# board.net
KiCad netlist of a schematic drawn in EAGLE
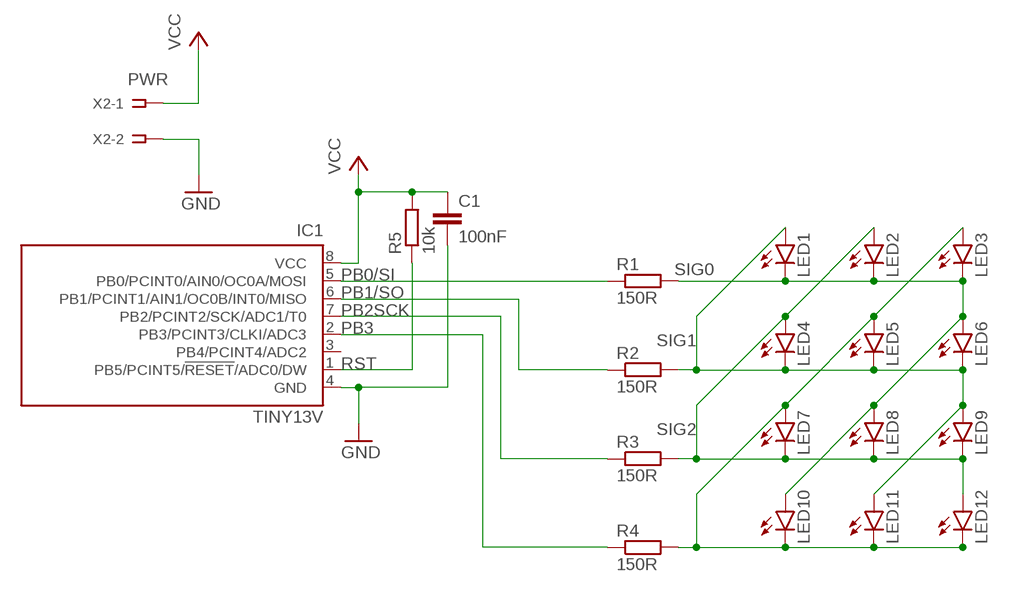
[diagram p0: schematic, sheet 1]

(export (version "E")
  (design (tool "Eeschema 10.0.6"))
  (components
    (comp (ref "C1")
      (value "100nF")
      (footprint "eagle-import:C1206K")
      (libsource (lib "eagle-import") (part "C-EUC1206K"))
    )
    (comp (ref "IC1")
      (value "TINY13V")
      (footprint "eagle-import:8S1")
      (fields (field (name "MPN") "ATTINY13V-10SSU"))
      (libsource (lib "eagle-import") (part "TINY13SSUV-10"))
    )
    (comp (ref "LED1")
      (value "LEDSFH480")
      (footprint "eagle-import:SFH480")
      (libsource (lib "eagle-import") (part "LEDSFH480"))
    )
    (comp (ref "LED2")
      (value "LEDSFH480")
      (footprint "eagle-import:SFH480")
      (libsource (lib "eagle-import") (part "LEDSFH480"))
    )
    (comp (ref "LED3")
      (value "LEDSFH480")
      (footprint "eagle-import:SFH480")
      (libsource (lib "eagle-import") (part "LEDSFH480"))
    )
    (comp (ref "LED4")
      (value "LEDSFH480")
      (footprint "eagle-import:SFH480")
      (libsource (lib "eagle-import") (part "LEDSFH480"))
    )
    (comp (ref "LED5")
      (value "LEDSFH480")
      (footprint "eagle-import:SFH480")
      (libsource (lib "eagle-import") (part "LEDSFH480"))
    )
    (comp (ref "LED6")
      (value "LEDSFH480")
      (footprint "eagle-import:SFH480")
      (libsource (lib "eagle-import") (part "LEDSFH480"))
    )
    (comp (ref "LED7")
      (value "LEDSFH480")
      (footprint "eagle-import:SFH480")
      (libsource (lib "eagle-import") (part "LEDSFH480"))
    )
    (comp (ref "LED8")
      (value "LEDSFH480")
      (footprint "eagle-import:SFH480")
      (libsource (lib "eagle-import") (part "LEDSFH480"))
    )
    (comp (ref "LED9")
      (value "LEDSFH480")
      (footprint "eagle-import:SFH480")
      (libsource (lib "eagle-import") (part "LEDSFH480"))
    )
    (comp (ref "LED10")
      (value "LEDSFH480")
      (footprint "eagle-import:SFH480")
      (libsource (lib "eagle-import") (part "LEDSFH480"))
    )
    (comp (ref "LED11")
      (value "LEDSFH480")
      (footprint "eagle-import:SFH480")
      (libsource (lib "eagle-import") (part "LEDSFH480"))
    )
    (comp (ref "LED12")
      (value "LEDSFH480")
      (footprint "eagle-import:SFH480")
      (libsource (lib "eagle-import") (part "LEDSFH480"))
    )
    (comp (ref "R1")
      (value "150R")
      (footprint "eagle-import:R1206")
      (libsource (lib "eagle-import") (part "R-EU_R1206"))
    )
    (comp (ref "R2")
      (value "150R")
      (footprint "eagle-import:R1206")
      (libsource (lib "eagle-import") (part "R-EU_R1206"))
    )
    (comp (ref "R3")
      (value "150R")
      (footprint "eagle-import:R1206")
      (libsource (lib "eagle-import") (part "R-EU_R1206"))
    )
    (comp (ref "R4")
      (value "150R")
      (footprint "eagle-import:R1206")
      (libsource (lib "eagle-import") (part "R-EU_R1206"))
    )
    (comp (ref "R5")
      (value "10k")
      (footprint "eagle-import:R1206")
      (libsource (lib "eagle-import") (part "R-EU_R1206"))
    )
    (comp (ref "X2")
      (value "PWR")
      (footprint "eagle-import:SSW-101-02-G-D")
      (fields (field (name "MF") "Samtec Inc.") (field (name "MPN") "SSW-101-02-G-D"))
      (libsource (lib "eagle-import") (part "SSW-101-02-G-D"))
    )
  )
  (nets
    (net (code "1") (name "/PB0{slash}SI") (class "Default")
      (node (ref "IC1") (pin "5") (pinfunction "PB0/PCINT0/AIN0/OC0A/MOSI_5") (pintype "bidirectional"))
      (node (ref "R1") (pin "1") (pinfunction "1_1") (pintype "passive"))
    )
    (net (code "2") (name "/PB1{slash}SO") (class "Default")
      (node (ref "IC1") (pin "6") (pinfunction "PB1/PCINT1/AIN1/OC0B/INT0/MISO_6") (pintype "bidirectional"))
      (node (ref "R2") (pin "1") (pinfunction "1_1") (pintype "passive"))
    )
    (net (code "3") (name "/PB2SCK") (class "Default")
      (node (ref "IC1") (pin "7") (pinfunction "PB2/PCINT2/SCK/ADC1/T0_7") (pintype "bidirectional"))
      (node (ref "R3") (pin "1") (pinfunction "1_1") (pintype "passive"))
    )
    (net (code "4") (name "/PB3") (class "Default")
      (node (ref "IC1") (pin "2") (pinfunction "PB3/PCINT3/CLKI/ADC3_2") (pintype "bidirectional"))
      (node (ref "R4") (pin "1") (pinfunction "1_1") (pintype "passive"))
    )
    (net (code "5") (name "/RST") (class "Default")
      (node (ref "IC1") (pin "1") (pinfunction "PB5/PCINT5/~{RESET}/ADC0/DW_1") (pintype "bidirectional"))
      (node (ref "R5") (pin "1") (pinfunction "1_1") (pintype "passive"))
    )
    (net (code "6") (name "/SIG0") (class "Default")
      (node (ref "LED1") (pin "K") (pinfunction "C_K") (pintype "passive"))
      (node (ref "LED10") (pin "A") (pinfunction "A_A") (pintype "passive"))
      (node (ref "LED2") (pin "K") (pinfunction "C_K") (pintype "passive"))
      (node (ref "LED3") (pin "K") (pinfunction "C_K") (pintype "passive"))
      (node (ref "LED6") (pin "A") (pinfunction "A_A") (pintype "passive"))
      (node (ref "LED8") (pin "A") (pinfunction "A_A") (pintype "passive"))
      (node (ref "R1") (pin "2") (pinfunction "2_2") (pintype "passive"))
    )
    (net (code "7") (name "/SIG1") (class "Default")
      (node (ref "LED1") (pin "A") (pinfunction "A_A") (pintype "passive"))
      (node (ref "LED11") (pin "A") (pinfunction "A_A") (pintype "passive"))
      (node (ref "LED4") (pin "K") (pinfunction "C_K") (pintype "passive"))
      (node (ref "LED5") (pin "K") (pinfunction "C_K") (pintype "passive"))
      (node (ref "LED6") (pin "K") (pinfunction "C_K") (pintype "passive"))
      (node (ref "LED9") (pin "A") (pinfunction "A_A") (pintype "passive"))
      (node (ref "R2") (pin "2") (pinfunction "2_2") (pintype "passive"))
    )
    (net (code "8") (name "/SIG2") (class "Default")
      (node (ref "LED12") (pin "A") (pinfunction "A_A") (pintype "passive"))
      (node (ref "LED2") (pin "A") (pinfunction "A_A") (pintype "passive"))
      (node (ref "LED4") (pin "A") (pinfunction "A_A") (pintype "passive"))
      (node (ref "LED7") (pin "K") (pinfunction "C_K") (pintype "passive"))
      (node (ref "LED8") (pin "K") (pinfunction "C_K") (pintype "passive"))
      (node (ref "LED9") (pin "K") (pinfunction "C_K") (pintype "passive"))
      (node (ref "R3") (pin "2") (pinfunction "2_2") (pintype "passive"))
    )
    (net (code "9") (name "GND") (class "Default")
      (node (ref "C1") (pin "2") (pinfunction "2_2") (pintype "passive"))
      (node (ref "IC1") (pin "4") (pinfunction "GND_4") (pintype "power_in"))
      (node (ref "X2") (pin "2") (pinfunction "1_2") (pintype "passive"))
    )
    (net (code "10") (name "Net-(LED10-C)") (class "Default")
      (node (ref "LED10") (pin "K") (pinfunction "C_K") (pintype "passive"))
      (node (ref "LED11") (pin "K") (pinfunction "C_K") (pintype "passive"))
      (node (ref "LED12") (pin "K") (pinfunction "C_K") (pintype "passive"))
      (node (ref "LED3") (pin "A") (pinfunction "A_A") (pintype "passive"))
      (node (ref "LED5") (pin "A") (pinfunction "A_A") (pintype "passive"))
      (node (ref "LED7") (pin "A") (pinfunction "A_A") (pintype "passive"))
      (node (ref "R4") (pin "2") (pinfunction "2_2") (pintype "passive"))
    )
    (net (code "11") (name "VCC") (class "Default")
      (node (ref "C1") (pin "1") (pinfunction "1_1") (pintype "passive"))
      (node (ref "IC1") (pin "8") (pinfunction "VCC_8") (pintype "power_in"))
      (node (ref "R5") (pin "2") (pinfunction "2_2") (pintype "passive"))
      (node (ref "X2") (pin "1") (pinfunction "1_1") (pintype "passive"))
    )
    (net (code "12") (name "unconnected-(IC1-PB4{slash}PCINT4{slash}ADC2-Pad3)") (class "Default")
      (node (ref "IC1") (pin "3") (pinfunction "PB4/PCINT4/ADC2_3") (pintype "bidirectional"))
    )
  )
)
